# receiver_schematic.net
KiCad netlist of a schematic drawn in EAGLE
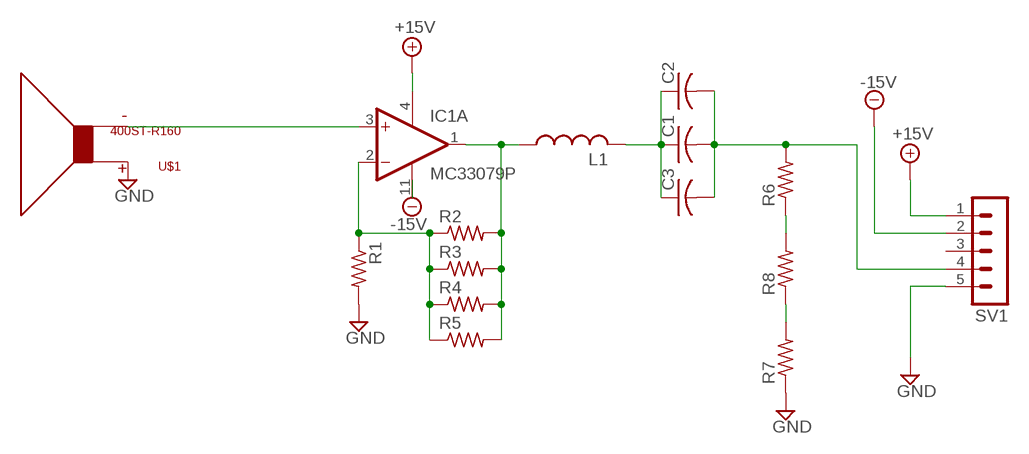
[diagram p0: schematic, sheet 1]

(export (version "E")
  (design (tool "Eeschema 10.0.6"))
  (components
    (comp (ref "C1")
      (value "C-US025-030X050")
      (footprint "eagle-import:C025-030X050")
      (libsource (lib "eagle-import") (part "C-US025-030X050"))
    )
    (comp (ref "C2")
      (value "C-US025-030X050")
      (footprint "eagle-import:C025-030X050")
      (libsource (lib "eagle-import") (part "C-US025-030X050"))
    )
    (comp (ref "C3")
      (value "C-US025-030X050")
      (footprint "eagle-import:C025-030X050")
      (libsource (lib "eagle-import") (part "C-US025-030X050"))
    )
    (comp (ref "IC1")
      (value "MC33079P")
      (footprint "eagle-import:DIL14")
      (libsource (lib "eagle-import") (part "MC33079P"))
    )
    (comp (ref "L1")
      (value "L-US0204/5")
      (footprint "eagle-import:0204_5")
      (libsource (lib "eagle-import") (part "L-US0204/5"))
    )
    (comp (ref "R1")
      (value "R-US_0204/5")
      (footprint "eagle-import:0204_5")
      (libsource (lib "eagle-import") (part "R-US_0204/5"))
    )
    (comp (ref "R2")
      (value "R-US_0204/5")
      (footprint "eagle-import:0204_5")
      (libsource (lib "eagle-import") (part "R-US_0204/5"))
    )
    (comp (ref "R3")
      (value "R-US_0204/5")
      (footprint "eagle-import:0204_5")
      (libsource (lib "eagle-import") (part "R-US_0204/5"))
    )
    (comp (ref "R4")
      (value "R-US_0204/5")
      (footprint "eagle-import:0204_5")
      (libsource (lib "eagle-import") (part "R-US_0204/5"))
    )
    (comp (ref "R5")
      (value "R-US_0204/5")
      (footprint "eagle-import:0204_5")
      (libsource (lib "eagle-import") (part "R-US_0204/5"))
    )
    (comp (ref "R6")
      (value "R-US_0204/5")
      (footprint "eagle-import:0204_5")
      (libsource (lib "eagle-import") (part "R-US_0204/5"))
    )
    (comp (ref "R7")
      (value "R-US_0204/5")
      (footprint "eagle-import:0204_5")
      (libsource (lib "eagle-import") (part "R-US_0204/5"))
    )
    (comp (ref "R8")
      (value "R-US_0204/5")
      (footprint "eagle-import:0204_5")
      (libsource (lib "eagle-import") (part "R-US_0204/5"))
    )
    (comp (ref "SV1")
      (value "MA05-1")
      (footprint "eagle-import:MA05-1")
      (libsource (lib "eagle-import") (part "MA05-1"))
    )
    (comp (ref "U$1")
      (value "400ST-R160")
      (footprint "eagle-import:400STR160")
      (libsource (lib "eagle-import") (part "400ST-R160"))
    )
  )
  (nets
    (net (code "1") (name "+15V") (class "Default")
      (node (ref "IC1") (pin "4") (pinfunction "V+_4") (pintype "power_in"))
      (node (ref "SV1") (pin "1") (pinfunction "1_1") (pintype "passive"))
    )
    (net (code "2") (name "-15V") (class "Default")
      (node (ref "IC1") (pin "11") (pinfunction "V-_11") (pintype "power_in"))
      (node (ref "SV1") (pin "2") (pinfunction "2_2") (pintype "passive"))
    )
    (net (code "3") (name "GND") (class "Default")
      (node (ref "R1") (pin "2") (pinfunction "2_2") (pintype "passive"))
      (node (ref "R7") (pin "1") (pinfunction "1_1") (pintype "passive"))
      (node (ref "SV1") (pin "5") (pinfunction "5_5") (pintype "passive"))
      (node (ref "U$1") (pin "P$1") (pinfunction "P$1_P$1") (pintype "bidirectional"))
    )
    (net (code "4") (name "Net-(C1-Pad1)") (class "Default")
      (node (ref "C1") (pin "1") (pinfunction "1_1") (pintype "passive"))
      (node (ref "C2") (pin "1") (pinfunction "1_1") (pintype "passive"))
      (node (ref "C3") (pin "1") (pinfunction "1_1") (pintype "passive"))
      (node (ref "L1") (pin "2") (pinfunction "2_2") (pintype "passive"))
    )
    (net (code "5") (name "Net-(C1-Pad2)") (class "Default")
      (node (ref "C1") (pin "2") (pinfunction "2_2") (pintype "passive"))
      (node (ref "C2") (pin "2") (pinfunction "2_2") (pintype "passive"))
      (node (ref "C3") (pin "2") (pinfunction "2_2") (pintype "passive"))
      (node (ref "R6") (pin "2") (pinfunction "2_2") (pintype "passive"))
      (node (ref "SV1") (pin "4") (pinfunction "4_4") (pintype "passive"))
    )
    (net (code "6") (name "Net-(IC1A-+IN)") (class "Default")
      (node (ref "IC1") (pin "3") (pinfunction "+IN_3") (pintype "input"))
      (node (ref "U$1") (pin "P$2") (pinfunction "P$2_P$2") (pintype "bidirectional"))
    )
    (net (code "7") (name "Net-(IC1A--IN)") (class "Default")
      (node (ref "IC1") (pin "2") (pinfunction "-IN_2") (pintype "input"))
      (node (ref "R1") (pin "1") (pinfunction "1_1") (pintype "passive"))
      (node (ref "R2") (pin "1") (pinfunction "1_1") (pintype "passive"))
      (node (ref "R3") (pin "1") (pinfunction "1_1") (pintype "passive"))
      (node (ref "R4") (pin "1") (pinfunction "1_1") (pintype "passive"))
      (node (ref "R5") (pin "1") (pinfunction "1_1") (pintype "passive"))
    )
    (net (code "8") (name "Net-(IC1A-OUT)") (class "Default")
      (node (ref "IC1") (pin "1") (pinfunction "OUT_1") (pintype "output"))
      (node (ref "L1") (pin "1") (pinfunction "1_1") (pintype "passive"))
      (node (ref "R2") (pin "2") (pinfunction "2_2") (pintype "passive"))
      (node (ref "R3") (pin "2") (pinfunction "2_2") (pintype "passive"))
      (node (ref "R4") (pin "2") (pinfunction "2_2") (pintype "passive"))
      (node (ref "R5") (pin "2") (pinfunction "2_2") (pintype "passive"))
    )
    (net (code "9") (name "Net-(R6-Pad1)") (class "Default")
      (node (ref "R6") (pin "1") (pinfunction "1_1") (pintype "passive"))
      (node (ref "R8") (pin "2") (pinfunction "2_2") (pintype "passive"))
    )
    (net (code "10") (name "Net-(R7-Pad2)") (class "Default")
      (node (ref "R7") (pin "2") (pinfunction "2_2") (pintype "passive"))
      (node (ref "R8") (pin "1") (pinfunction "1_1") (pintype "passive"))
    )
    (net (code "11") (name "unconnected-(SV1-Pad3)") (class "Default")
      (node (ref "SV1") (pin "3") (pinfunction "3_3") (pintype "passive"))
    )
  )
)
